# FEM.net
KiCad netlist of a schematic drawn in Altium Designer
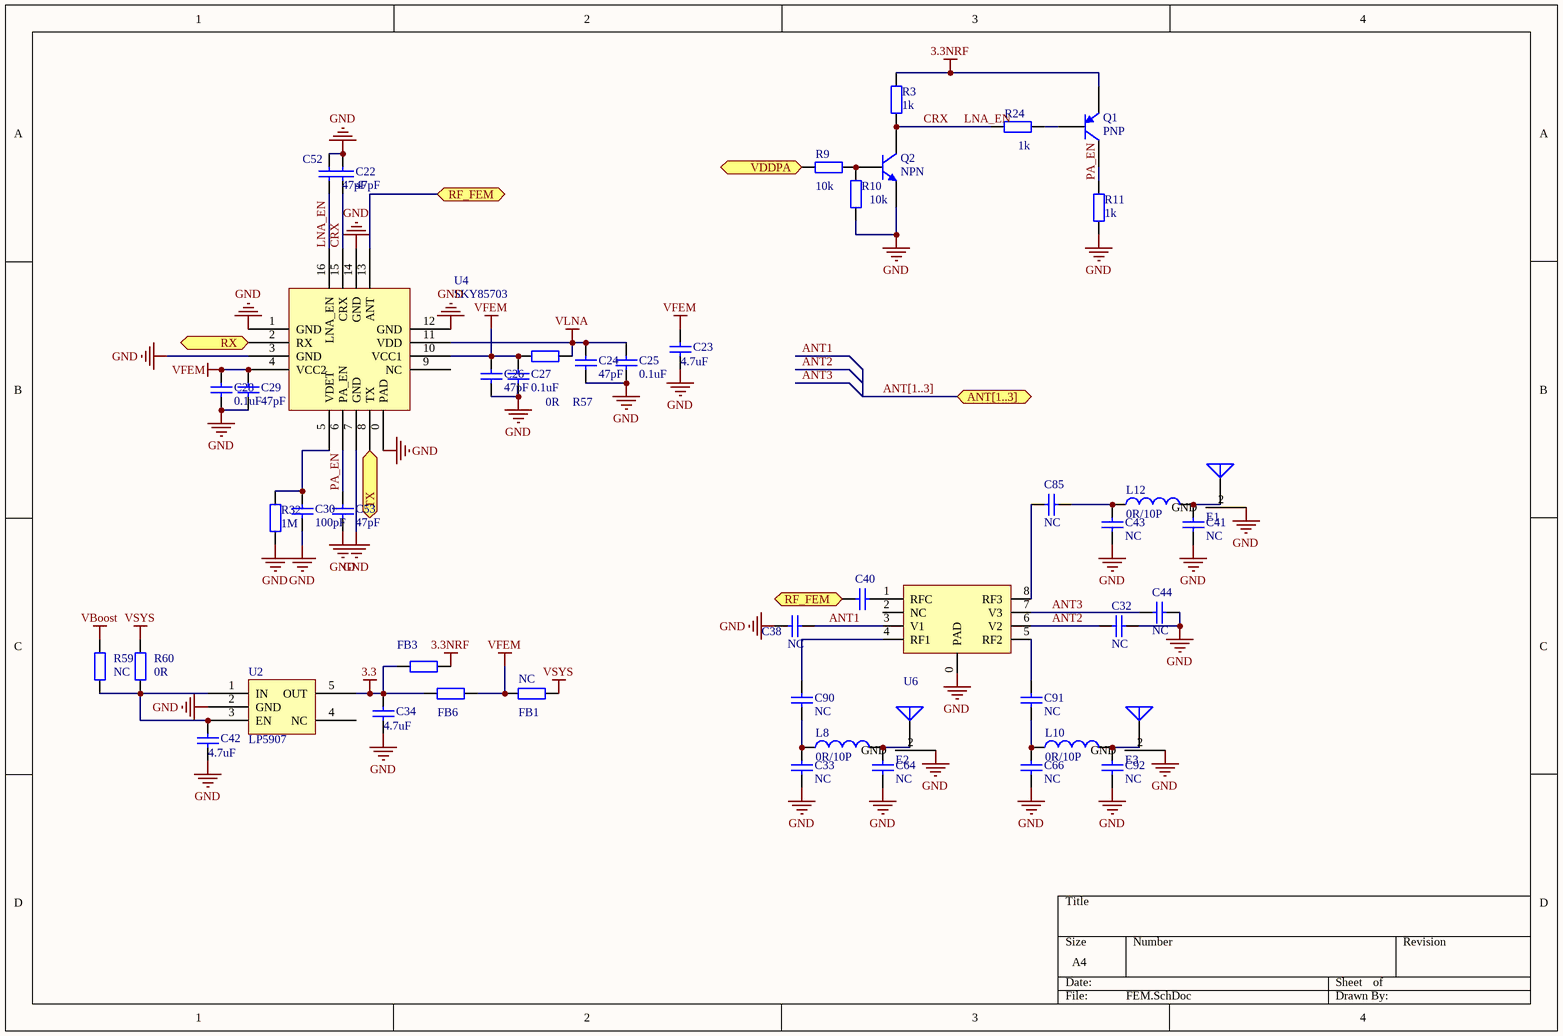
[diagram p0: FEM.SchDoc]

(export (version "E")
  (design (tool "Eeschema 10.0.6"))
  (components
    (comp (ref "C22")
      (value "47pF")
      (footprint "0402")
      (description "Capacitor")
      (fields (field (name "PUBLISHER") "Altium Limited"))
      (libsource (lib "RTC6705") (part "Cap"))
    )
    (comp (ref "C23")
      (value "4.7uF")
      (footprint "0805")
      (description "Capacitor")
      (fields (field (name "PUBLISHER") "Altium Limited"))
      (libsource (lib "RTC6705") (part "Cap"))
    )
    (comp (ref "C24")
      (value "47pF")
      (footprint "0402")
      (description "Capacitor")
      (fields (field (name "PUBLISHER") "Altium Limited"))
      (libsource (lib "RTC6705") (part "Cap"))
    )
    (comp (ref "C25")
      (value "0.1uF")
      (footprint "0402")
      (description "Capacitor")
      (fields (field (name "PUBLISHER") "Altium Limited"))
      (libsource (lib "RTC6705") (part "Cap"))
    )
    (comp (ref "C26")
      (value "47pF")
      (footprint "0402")
      (description "Capacitor")
      (fields (field (name "PUBLISHER") "Altium Limited"))
      (libsource (lib "RTC6705") (part "Cap"))
    )
    (comp (ref "C27")
      (value "0.1uF")
      (footprint "0402")
      (description "Capacitor")
      (fields (field (name "PUBLISHER") "Altium Limited"))
      (libsource (lib "RTC6705") (part "Cap"))
    )
    (comp (ref "C28")
      (value "0.1uF")
      (footprint "0402")
      (description "Capacitor")
      (fields (field (name "PUBLISHER") "Altium Limited"))
      (libsource (lib "RTC6705") (part "Cap"))
    )
    (comp (ref "C29")
      (value "47pF")
      (footprint "0402")
      (description "Capacitor")
      (fields (field (name "PUBLISHER") "Altium Limited"))
      (libsource (lib "RTC6705") (part "Cap"))
    )
    (comp (ref "C30")
      (value "100pF")
      (footprint "0402")
      (description "Capacitor")
      (fields (field (name "PUBLISHER") "Altium Limited"))
      (libsource (lib "RTC6705") (part "Cap"))
    )
    (comp (ref "C32")
      (value "NC")
      (footprint "0402")
      (description "Capacitor")
      (fields (field (name "Comment") "Cap") (field (name "PUBLISHER") "Altium Limited"))
      (libsource (lib "RTC6705") (part "Cap"))
    )
    (comp (ref "C33")
      (value "NC")
      (footprint "0402")
      (description "Capacitor")
      (fields (field (name "Comment") "Cap") (field (name "PUBLISHER") "Altium Limited"))
      (libsource (lib "RTC6705") (part "Cap"))
    )
    (comp (ref "C34")
      (value "4.7uF")
      (footprint "0603")
      (description "Capacitor")
      (fields (field (name "PUBLISHER") "Altium Limited"))
      (libsource (lib "RTC6705") (part "Cap"))
    )
    (comp (ref "C38")
      (value "NC")
      (footprint "0402")
      (description "Capacitor")
      (fields (field (name "Comment") "Cap") (field (name "PUBLISHER") "Altium Limited"))
      (libsource (lib "RTC6705") (part "Cap"))
    )
    (comp (ref "C40")
      (value "10p")
      (footprint "0402")
      (description "Capacitor")
      (fields (field (name "PUBLISHER") "Altium Limited"))
      (libsource (lib "RTC6705") (part "Cap"))
    )
    (comp (ref "C41")
      (value "NC")
      (footprint "0402")
      (description "Capacitor")
      (fields (field (name "Comment") "Cap") (field (name "PUBLISHER") "Altium Limited"))
      (libsource (lib "RTC6705") (part "Cap"))
    )
    (comp (ref "C42")
      (value "4.7uF")
      (footprint "0603")
      (description "Capacitor")
      (fields (field (name "PUBLISHER") "Altium Limited"))
      (libsource (lib "RTC6705") (part "Cap"))
    )
    (comp (ref "C43")
      (value "NC")
      (footprint "0402")
      (description "Capacitor")
      (fields (field (name "Comment") "Cap") (field (name "PUBLISHER") "Altium Limited"))
      (libsource (lib "RTC6705") (part "Cap"))
    )
    (comp (ref "C44")
      (value "NC")
      (footprint "0402")
      (description "Capacitor")
      (fields (field (name "Comment") "Cap") (field (name "PUBLISHER") "Altium Limited"))
      (libsource (lib "RTC6705") (part "Cap"))
    )
    (comp (ref "C52")
      (value "47pF")
      (footprint "0402")
      (description "Capacitor")
      (fields (field (name "PUBLISHER") "Altium Limited"))
      (libsource (lib "RTC6705") (part "Cap"))
    )
    (comp (ref "C53")
      (value "47pF")
      (footprint "0402")
      (description "Capacitor")
      (fields (field (name "PUBLISHER") "Altium Limited"))
      (libsource (lib "RTC6705") (part "Cap"))
    )
    (comp (ref "C64")
      (value "NC")
      (footprint "0402")
      (description "Capacitor")
      (fields (field (name "Comment") "Cap") (field (name "PUBLISHER") "Altium Limited"))
      (libsource (lib "RTC6705") (part "Cap"))
    )
    (comp (ref "C66")
      (value "NC")
      (footprint "0402")
      (description "Capacitor")
      (fields (field (name "Comment") "Cap") (field (name "PUBLISHER") "Altium Limited"))
      (libsource (lib "RTC6705") (part "Cap"))
    )
    (comp (ref "C85")
      (value "NC")
      (footprint "0402")
      (description "Capacitor")
      (fields (field (name "Comment") "Cap") (field (name "PUBLISHER") "Altium Limited"))
      (libsource (lib "RTC6705") (part "Cap"))
    )
    (comp (ref "C90")
      (value "NC")
      (footprint "0402")
      (description "Capacitor")
      (fields (field (name "Comment") "Cap") (field (name "PUBLISHER") "Altium Limited"))
      (libsource (lib "RTC6705") (part "Cap"))
    )
    (comp (ref "C91")
      (value "NC")
      (footprint "0402")
      (description "Capacitor")
      (fields (field (name "Comment") "Cap") (field (name "PUBLISHER") "Altium Limited"))
      (libsource (lib "RTC6705") (part "Cap"))
    )
    (comp (ref "C92")
      (value "NC")
      (footprint "0402")
      (description "Capacitor")
      (fields (field (name "Comment") "Cap") (field (name "PUBLISHER") "Altium Limited"))
      (libsource (lib "RTC6705") (part "Cap"))
    )
    (comp (ref "E1")
      (value "Antenna")
      (footprint "IPEX")
      (description "Generic Antenna")
      (fields (field (name "PUBLISHER") "Altium Limited"))
      (libsource (lib "Miscellaneous Devices") (part "Antenna"))
    )
    (comp (ref "E2")
      (value "Antenna")
      (footprint "IPEX")
      (description "Generic Antenna")
      (fields (field (name "PUBLISHER") "Altium Limited"))
      (libsource (lib "Miscellaneous Devices") (part "Antenna"))
    )
    (comp (ref "E3")
      (value "Antenna")
      (footprint "IPEX")
      (description "Generic Antenna")
      (fields (field (name "PUBLISHER") "Altium Limited"))
      (libsource (lib "Miscellaneous Devices") (part "Antenna"))
    )
    (comp (ref "FB1")
      (value "NC")
      (footprint "0402")
      (description "Resistor")
      (fields (field (name "PUBLISHER") "Altium Limited"))
      (libsource (lib "RTC6705") (part "Res2"))
    )
    (comp (ref "FB3")
      (value "Res2")
      (footprint "0402")
      (description "Resistor")
      (fields (field (name "PUBLISHER") "Altium Limited"))
      (libsource (lib "RTC6705") (part "Res2"))
    )
    (comp (ref "FB6")
      (value "Res2")
      (footprint "0402")
      (description "Resistor")
      (fields (field (name "PUBLISHER") "Altium Limited"))
      (libsource (lib "RTC6705") (part "Res2"))
    )
    (comp (ref "L8")
      (value "0R/10P")
      (footprint "0402")
      (description "Inductor")
      (fields (field (name "PUBLISHER") "Altium Limited"))
      (libsource (lib "Miscellaneous Devices") (part "Inductor"))
    )
    (comp (ref "L10")
      (value "0R/10P")
      (footprint "0402")
      (description "Inductor")
      (fields (field (name "PUBLISHER") "Altium Limited"))
      (libsource (lib "Miscellaneous Devices") (part "Inductor"))
    )
    (comp (ref "L12")
      (value "0R/10P")
      (footprint "0402")
      (description "Inductor")
      (fields (field (name "PUBLISHER") "Altium Limited"))
      (libsource (lib "Miscellaneous Devices") (part "Inductor"))
    )
    (comp (ref "Q1")
      (value "PNP")
      (footprint "LC-SOT-323(SC-70)")
      (description "PNP Bipolar Transistor")
      (fields (field (name "PUBLISHER") "Altium Limited"))
      (libsource (lib "BK5811FEM") (part "PNP"))
    )
    (comp (ref "Q2")
      (value "NPN")
      (footprint "LC-SOT-323(SC-70)")
      (description "NPN Bipolar Transistor")
      (fields (field (name "PUBLISHER") "Altium Limited"))
      (libsource (lib "BK5811FEM") (part "NPN"))
    )
    (comp (ref "R3")
      (value "1k")
      (footprint "0402")
      (description "Resistor")
      (fields (field (name "Comment") "Res2") (field (name "PUBLISHER") "Altium Limited"))
      (libsource (lib "") (part "Res2_2"))
    )
    (comp (ref "R9")
      (value "10k")
      (footprint "0402")
      (description "Resistor")
      (fields (field (name "PUBLISHER") "Altium Limited"))
      (libsource (lib "RTC6705") (part "Res2"))
    )
    (comp (ref "R10")
      (value "10k")
      (footprint "0402")
      (description "Resistor")
      (fields (field (name "PUBLISHER") "Altium Limited"))
      (libsource (lib "") (part "Res2_1"))
    )
    (comp (ref "R11")
      (value "1k")
      (footprint "0402")
      (description "Resistor")
      (fields (field (name "Comment") "Res2") (field (name "PUBLISHER") "Altium Limited"))
      (libsource (lib "") (part "Res2_1"))
    )
    (comp (ref "R24")
      (value "1k")
      (footprint "0402")
      (description "Resistor")
      (fields (field (name "Comment") "Res2") (field (name "PUBLISHER") "Altium Limited"))
      (libsource (lib "RTC6705") (part "Res2"))
    )
    (comp (ref "R32")
      (value "1M")
      (footprint "0402")
      (description "Resistor")
      (fields (field (name "Comment") "Res2") (field (name "PUBLISHER") "Altium Limited"))
      (libsource (lib "") (part "Res2_2"))
    )
    (comp (ref "R57")
      (value "0R")
      (footprint "0402")
      (description "Resistor")
      (fields (field (name "PUBLISHER") "Altium Limited"))
      (libsource (lib "RTC6705") (part "Res2"))
    )
    (comp (ref "R59")
      (value "NC")
      (footprint "0402")
      (description "Resistor")
      (fields (field (name "PUBLISHER") "Altium Limited"))
      (libsource (lib "") (part "Res2_1"))
    )
    (comp (ref "R60")
      (value "0R")
      (footprint "0402")
      (description "Resistor")
      (fields (field (name "PUBLISHER") "Altium Limited"))
      (libsource (lib "") (part "Res2_1"))
    )
    (comp (ref "U2") (value "LP5907") (footprint "SOT23-5") (libsource (lib "RTC6705") (part "LP5907")))
    (comp (ref "U4") (value "SKY85703") (footprint "QFN16-3x3") (libsource (lib "BK5811") (part "SKY85703")))
    (comp (ref "U6") (value "SKY13417") (footprint "SKY13317") (libsource (lib "F4SDR") (part "SKY13417")))
  )
  (nets
    (net (code "1") (name "/ANT1") (class "Default")
      (node (ref "C38") (pin "2") (pinfunction "2_2") (pintype "passive"))
      (node (ref "U6") (pin "3") (pinfunction "V1_3") (pintype "passive"))
    )
    (net (code "2") (name "/ANT2") (class "Default")
      (node (ref "C32") (pin "2") (pinfunction "2_2") (pintype "passive"))
      (node (ref "U6") (pin "6") (pinfunction "V2_6") (pintype "passive"))
    )
    (net (code "3") (name "/ANT3") (class "Default")
      (node (ref "C44") (pin "2") (pinfunction "2_2") (pintype "passive"))
      (node (ref "U6") (pin "7") (pinfunction "V3_7") (pintype "passive"))
    )
    (net (code "5") (name "/CRX") (class "Default")
      (node (ref "C22") (pin "2") (pinfunction "2_2") (pintype "passive"))
      (node (ref "C52") (pin "1") (pinfunction "1_1") (pintype "passive"))
      (node (ref "Q2") (pin "3") (pinfunction "C_3") (pintype "passive"))
      (node (ref "R24") (pin "1") (pinfunction "1_1") (pintype "passive"))
      (node (ref "R3") (pin "2") (pinfunction "2_2") (pintype "passive"))
      (node (ref "U4") (pin "15") (pinfunction "CRX_15") (pintype "passive"))
      (node (ref "U4") (pin "16") (pinfunction "LNA_EN_16") (pintype "passive"))
    )
    (net (code "6") (name "/PA_EN") (class "Default")
      (node (ref "C53") (pin "2") (pinfunction "2_2") (pintype "passive"))
      (node (ref "Q1") (pin "3") (pinfunction "C_3") (pintype "passive"))
      (node (ref "R11") (pin "2") (pinfunction "2_2") (pintype "passive"))
      (node (ref "U4") (pin "6") (pinfunction "PA_EN_6") (pintype "passive"))
    )
    (net (code "7") (name "/RF_FEM") (class "Default")
      (node (ref "C40") (pin "2") (pinfunction "2_2") (pintype "passive"))
      (node (ref "U4") (pin "13") (pinfunction "ANT_13") (pintype "passive"))
    )
    (net (code "8") (name "/RX") (class "Default")
      (node (ref "U4") (pin "2") (pinfunction "RX_2") (pintype "passive"))
    )
    (net (code "9") (name "/TX") (class "Default")
      (node (ref "U4") (pin "8") (pinfunction "TX_8") (pintype "passive"))
    )
    (net (code "10") (name "/VDDPA") (class "Default")
      (node (ref "R9") (pin "1") (pinfunction "1_1") (pintype "passive"))
    )
    (net (code "11") (name "3.3") (class "Default")
      (node (ref "C34") (pin "2") (pinfunction "2_2") (pintype "passive"))
      (node (ref "FB3") (pin "1") (pinfunction "1_1") (pintype "passive"))
      (node (ref "FB6") (pin "1") (pinfunction "1_1") (pintype "passive"))
      (node (ref "U2") (pin "5") (pinfunction "OUT_5") (pintype "passive"))
    )
    (net (code "12") (name "3.3NRF") (class "Default")
      (node (ref "FB3") (pin "2") (pinfunction "2_2") (pintype "passive"))
      (node (ref "Q1") (pin "2") (pinfunction "E_2") (pintype "passive"))
      (node (ref "R3") (pin "1") (pinfunction "1_1") (pintype "passive"))
    )
    (net (code "13") (name "GND") (class "Default")
      (node (ref "C22") (pin "1") (pinfunction "1_1") (pintype "passive"))
      (node (ref "C23") (pin "1") (pinfunction "1_1") (pintype "passive"))
      (node (ref "C24") (pin "1") (pinfunction "1_1") (pintype "passive"))
      (node (ref "C25") (pin "1") (pinfunction "1_1") (pintype "passive"))
      (node (ref "C26") (pin "1") (pinfunction "1_1") (pintype "passive"))
      (node (ref "C27") (pin "1") (pinfunction "1_1") (pintype "passive"))
      (node (ref "C28") (pin "1") (pinfunction "1_1") (pintype "passive"))
      (node (ref "C29") (pin "1") (pinfunction "1_1") (pintype "passive"))
      (node (ref "C30") (pin "1") (pinfunction "1_1") (pintype "passive"))
      (node (ref "C32") (pin "1") (pinfunction "1_1") (pintype "passive"))
      (node (ref "C33") (pin "2") (pinfunction "2_2") (pintype "passive"))
      (node (ref "C34") (pin "1") (pinfunction "1_1") (pintype "passive"))
      (node (ref "C38") (pin "1") (pinfunction "1_1") (pintype "passive"))
      (node (ref "C41") (pin "2") (pinfunction "2_2") (pintype "passive"))
      (node (ref "C42") (pin "1") (pinfunction "1_1") (pintype "passive"))
      (node (ref "C43") (pin "2") (pinfunction "2_2") (pintype "passive"))
      (node (ref "C44") (pin "1") (pinfunction "1_1") (pintype "passive"))
      (node (ref "C52") (pin "2") (pinfunction "2_2") (pintype "passive"))
      (node (ref "C53") (pin "1") (pinfunction "1_1") (pintype "passive"))
      (node (ref "C64") (pin "2") (pinfunction "2_2") (pintype "passive"))
      (node (ref "C66") (pin "2") (pinfunction "2_2") (pintype "passive"))
      (node (ref "C92") (pin "2") (pinfunction "2_2") (pintype "passive"))
      (node (ref "E1") (pin "2") (pinfunction "GND_2") (pintype "passive"))
      (node (ref "E2") (pin "2") (pinfunction "GND_2") (pintype "passive"))
      (node (ref "E3") (pin "2") (pinfunction "GND_2") (pintype "passive"))
      (node (ref "Q2") (pin "2") (pinfunction "E_2") (pintype "passive"))
      (node (ref "R10") (pin "1") (pinfunction "1_1") (pintype "passive"))
      (node (ref "R11") (pin "1") (pinfunction "1_1") (pintype "passive"))
      (node (ref "R32") (pin "2") (pinfunction "2_2") (pintype "passive"))
      (node (ref "U2") (pin "2") (pinfunction "GND_2") (pintype "passive"))
      (node (ref "U4") (pin "0") (pinfunction "PAD_0") (pintype "passive"))
      (node (ref "U4") (pin "1") (pinfunction "GND_1") (pintype "passive"))
      (node (ref "U4") (pin "12") (pinfunction "GND_12") (pintype "passive"))
      (node (ref "U4") (pin "14") (pinfunction "GND_14") (pintype "passive"))
      (node (ref "U4") (pin "3") (pinfunction "GND_3") (pintype "passive"))
      (node (ref "U4") (pin "7") (pinfunction "GND_7") (pintype "passive"))
      (node (ref "U6") (pin "0") (pinfunction "PAD_0") (pintype "passive"))
    )
    (net (code "14") (name "Net-(C33-Pad1)") (class "Default")
      (node (ref "C33") (pin "1") (pinfunction "1_1") (pintype "passive"))
      (node (ref "C90") (pin "2") (pinfunction "2_2") (pintype "passive"))
      (node (ref "L8") (pin "1") (pinfunction "1_1") (pintype "passive"))
    )
    (net (code "15") (name "Net-(C43-Pad1)") (class "Default")
      (node (ref "C43") (pin "1") (pinfunction "1_1") (pintype "passive"))
      (node (ref "C85") (pin "2") (pinfunction "2_2") (pintype "passive"))
      (node (ref "L12") (pin "1") (pinfunction "1_1") (pintype "passive"))
    )
    (net (code "16") (name "Net-(C66-Pad1)") (class "Default")
      (node (ref "C66") (pin "1") (pinfunction "1_1") (pintype "passive"))
      (node (ref "C91") (pin "2") (pinfunction "2_2") (pintype "passive"))
      (node (ref "L10") (pin "1") (pinfunction "1_1") (pintype "passive"))
    )
    (net (code "17") (name "Net-(E1-ANT)") (class "Default")
      (node (ref "C41") (pin "1") (pinfunction "1_1") (pintype "passive"))
      (node (ref "E1") (pin "1") (pinfunction "ANT_1") (pintype "passive"))
      (node (ref "L12") (pin "2") (pinfunction "2_2") (pintype "passive"))
    )
    (net (code "18") (name "Net-(E2-ANT)") (class "Default")
      (node (ref "C64") (pin "1") (pinfunction "1_1") (pintype "passive"))
      (node (ref "E2") (pin "1") (pinfunction "ANT_1") (pintype "passive"))
      (node (ref "L8") (pin "2") (pinfunction "2_2") (pintype "passive"))
    )
    (net (code "19") (name "Net-(E3-ANT)") (class "Default")
      (node (ref "C92") (pin "1") (pinfunction "1_1") (pintype "passive"))
      (node (ref "E3") (pin "1") (pinfunction "ANT_1") (pintype "passive"))
      (node (ref "L10") (pin "2") (pinfunction "2_2") (pintype "passive"))
    )
    (net (code "20") (name "Net-(Q1-B)") (class "Default")
      (node (ref "Q1") (pin "1") (pinfunction "B_1") (pintype "passive"))
      (node (ref "R24") (pin "2") (pinfunction "2_2") (pintype "passive"))
    )
    (net (code "21") (name "Net-(Q2-B)") (class "Default")
      (node (ref "Q2") (pin "1") (pinfunction "B_1") (pintype "passive"))
      (node (ref "R10") (pin "2") (pinfunction "2_2") (pintype "passive"))
      (node (ref "R9") (pin "2") (pinfunction "2_2") (pintype "passive"))
    )
    (net (code "22") (name "Net-(U2-EN)") (class "Default")
      (node (ref "C42") (pin "2") (pinfunction "2_2") (pintype "passive"))
      (node (ref "R59") (pin "1") (pinfunction "1_1") (pintype "passive"))
      (node (ref "R60") (pin "1") (pinfunction "1_1") (pintype "passive"))
      (node (ref "U2") (pin "1") (pinfunction "IN_1") (pintype "passive"))
      (node (ref "U2") (pin "3") (pinfunction "EN_3") (pintype "passive"))
    )
    (net (code "23") (name "Net-(U4-VDET)") (class "Default")
      (node (ref "C30") (pin "2") (pinfunction "2_2") (pintype "passive"))
      (node (ref "R32") (pin "1") (pinfunction "1_1") (pintype "passive"))
      (node (ref "U4") (pin "5") (pinfunction "VDET_5") (pintype "passive"))
    )
    (net (code "24") (name "Net-(U6-RF1)") (class "Default")
      (node (ref "C90") (pin "1") (pinfunction "1_1") (pintype "passive"))
      (node (ref "U6") (pin "4") (pinfunction "RF1_4") (pintype "passive"))
    )
    (net (code "25") (name "Net-(U6-RF2)") (class "Default")
      (node (ref "C91") (pin "1") (pinfunction "1_1") (pintype "passive"))
      (node (ref "U6") (pin "5") (pinfunction "RF2_5") (pintype "passive"))
    )
    (net (code "26") (name "Net-(U6-RF3)") (class "Default")
      (node (ref "C85") (pin "1") (pinfunction "1_1") (pintype "passive"))
      (node (ref "U6") (pin "8") (pinfunction "RF3_8") (pintype "passive"))
    )
    (net (code "27") (name "Net-(U6-RFC)") (class "Default")
      (node (ref "C40") (pin "1") (pinfunction "1_1") (pintype "passive"))
      (node (ref "U6") (pin "1") (pinfunction "RFC_1") (pintype "passive"))
    )
    (net (code "28") (name "VBoost") (class "Default")
      (node (ref "R59") (pin "2") (pinfunction "2_2") (pintype "passive"))
    )
    (net (code "29") (name "VFEM") (class "Default")
      (node (ref "C23") (pin "2") (pinfunction "2_2") (pintype "passive"))
      (node (ref "C26") (pin "2") (pinfunction "2_2") (pintype "passive"))
      (node (ref "C27") (pin "2") (pinfunction "2_2") (pintype "passive"))
      (node (ref "C28") (pin "2") (pinfunction "2_2") (pintype "passive"))
      (node (ref "C29") (pin "2") (pinfunction "2_2") (pintype "passive"))
      (node (ref "FB1") (pin "1") (pinfunction "1_1") (pintype "passive"))
      (node (ref "FB6") (pin "2") (pinfunction "2_2") (pintype "passive"))
      (node (ref "R57") (pin "1") (pinfunction "1_1") (pintype "passive"))
      (node (ref "U4") (pin "10") (pinfunction "VCC1_10") (pintype "passive"))
      (node (ref "U4") (pin "4") (pinfunction "VCC2_4") (pintype "passive"))
    )
    (net (code "30") (name "VLNA") (class "Default")
      (node (ref "C24") (pin "2") (pinfunction "2_2") (pintype "passive"))
      (node (ref "C25") (pin "2") (pinfunction "2_2") (pintype "passive"))
      (node (ref "R57") (pin "2") (pinfunction "2_2") (pintype "passive"))
      (node (ref "U4") (pin "11") (pinfunction "VDD_11") (pintype "passive"))
    )
    (net (code "31") (name "VSYS") (class "Default")
      (node (ref "FB1") (pin "2") (pinfunction "2_2") (pintype "passive"))
      (node (ref "R60") (pin "2") (pinfunction "2_2") (pintype "passive"))
    )
    (net (code "32") (name "unconnected-(U2-NC-Pad4)") (class "Default")
      (node (ref "U2") (pin "4") (pinfunction "NC_4") (pintype "passive"))
    )
    (net (code "33") (name "unconnected-(U4-NC-Pad9)") (class "Default")
      (node (ref "U4") (pin "9") (pinfunction "NC_9") (pintype "passive"))
    )
    (net (code "34") (name "unconnected-(U6-NC-Pad2)") (class "Default")
      (node (ref "U6") (pin "2") (pinfunction "NC_2") (pintype "passive"))
    )
  )
)
